# DC_Sensor_ESP8266_ADC_NC_10.net
KiCad netlist of a schematic drawn in EAGLE
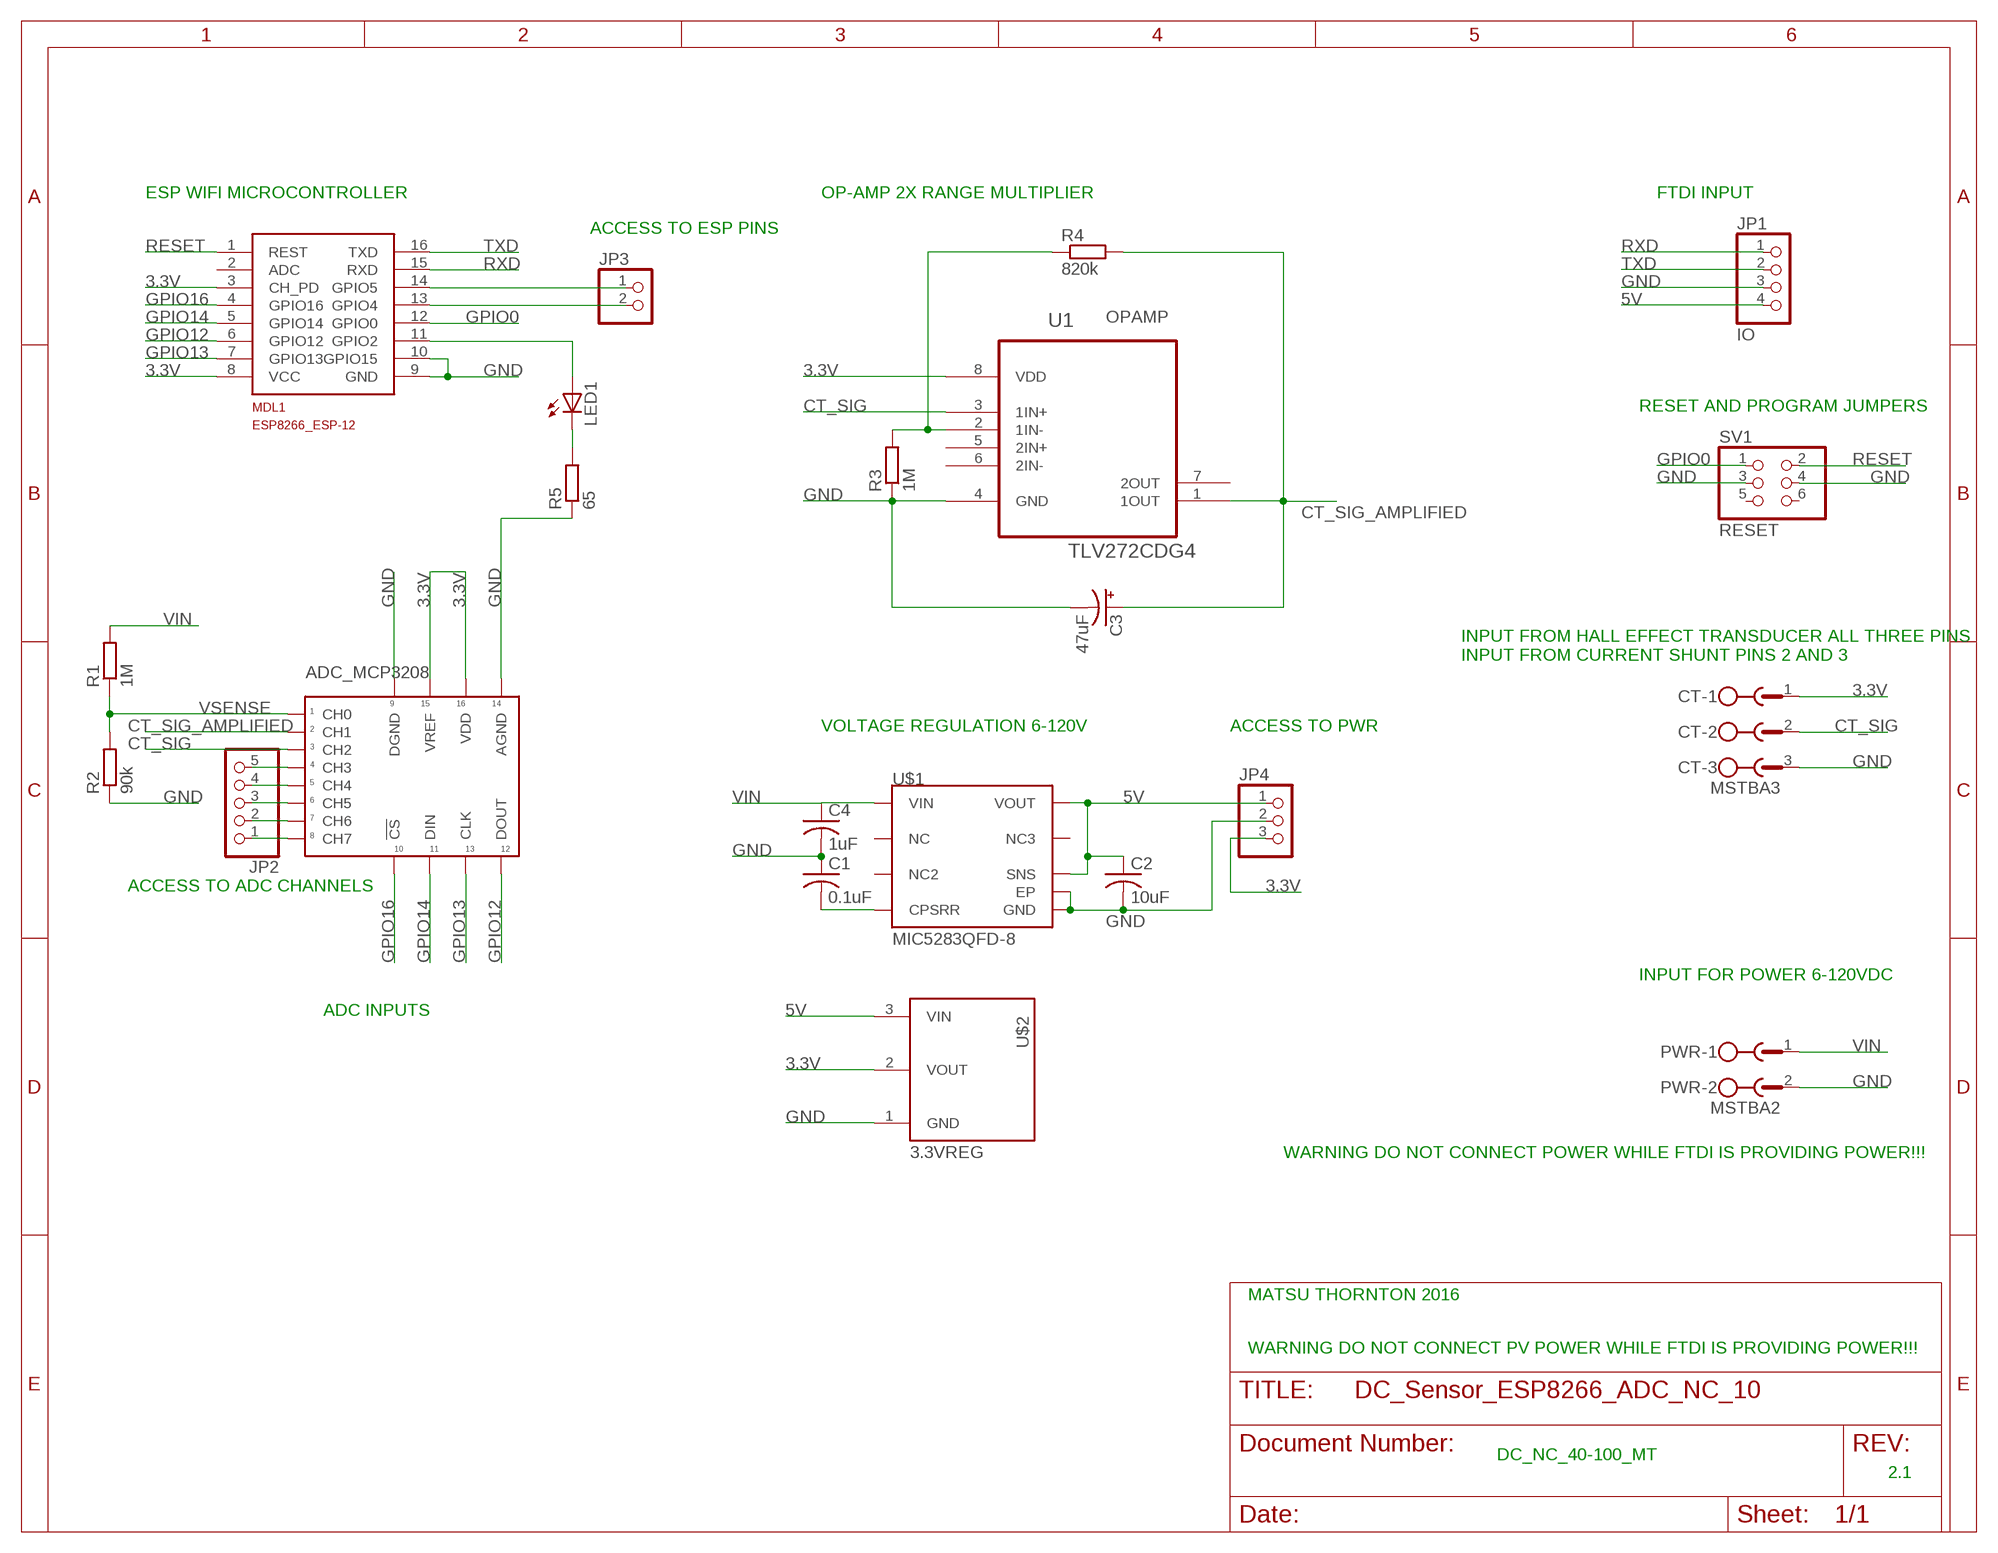
[diagram p0: schematic, sheet 1]

(export (version "E")
  (design (tool "Eeschema 10.0.6"))
  (components
    (comp (ref "ADC_MCP3208")
      (value "21298ESMD")
      (footprint "eagle-import:PDIP16")
      (libsource (lib "eagle-import") (part "21298ESMD"))
    )
    (comp (ref "C1")
      (value "0.1uF")
      (footprint "eagle-import:C0402")
      (libsource (lib "eagle-import") (part "C-USC0402"))
    )
    (comp (ref "C2")
      (value "10uF")
      (footprint "eagle-import:C0603K")
      (libsource (lib "eagle-import") (part "C-USC0603K"))
    )
    (comp (ref "C3")
      (value "47uF")
      (footprint "eagle-import:PANASONIC_C")
      (libsource (lib "eagle-import") (part "CPOL-USC"))
    )
    (comp (ref "C4")
      (value "1uF")
      (footprint "eagle-import:C2220K")
      (libsource (lib "eagle-import") (part "C-USC2220K"))
    )
    (comp (ref "CT")
      (value "MSTBA3")
      (footprint "eagle-import:MSTBA3")
      (fields (field (name "MF") "FARNELL") (field (name "MPN") "1757255"))
      (libsource (lib "eagle-import") (part "MSTBA3"))
    )
    (comp (ref "JP1")
      (value "IO")
      (footprint "eagle-import:1X04")
      (libsource (lib "eagle-import") (part "PINHD-1X4"))
    )
    (comp (ref "JP2")
      (value "PINHD-1X5")
      (footprint "eagle-import:1X05")
      (libsource (lib "eagle-import") (part "PINHD-1X5"))
    )
    (comp (ref "JP3")
      (value "PINHD-1X2")
      (footprint "eagle-import:1X02")
      (libsource (lib "eagle-import") (part "PINHD-1X2"))
    )
    (comp (ref "JP4")
      (value "PINHD-1X3")
      (footprint "eagle-import:1X03")
      (libsource (lib "eagle-import") (part "PINHD-1X3"))
    )
    (comp (ref "LED1")
      (value "LEDCHIP-LED0603")
      (footprint "eagle-import:CHIP-LED0603")
      (libsource (lib "eagle-import") (part "LEDCHIP-LED0603"))
    )
    (comp (ref "MDL1")
      (value "ESP8266-12GPIO04/05_CORRECTED")
      (footprint "eagle-import:ESP8266-ESP12")
      (libsource (lib "eagle-import") (part "ESP8266-12GPIO04/05_CORRECTED"))
    )
    (comp (ref "PWR")
      (value "MSTBA2")
      (footprint "eagle-import:MSTBA2")
      (fields (field (name "MF") "FARNELL") (field (name "MPN") "1757242"))
      (libsource (lib "eagle-import") (part "MSTBA2"))
    )
    (comp (ref "R1")
      (value "1M")
      (footprint "eagle-import:R0805")
      (libsource (lib "eagle-import") (part "R-EU_R0805"))
    )
    (comp (ref "R2")
      (value "90k")
      (footprint "eagle-import:R0805")
      (libsource (lib "eagle-import") (part "R-EU_R0805"))
    )
    (comp (ref "R3")
      (value "1M")
      (footprint "eagle-import:R0805")
      (libsource (lib "eagle-import") (part "R-EU_R0805"))
    )
    (comp (ref "R4")
      (value "820k")
      (footprint "eagle-import:R0805")
      (libsource (lib "eagle-import") (part "R-EU_R0805"))
    )
    (comp (ref "R5")
      (value "65")
      (footprint "eagle-import:R0805")
      (libsource (lib "eagle-import") (part "R-EU_R0805"))
    )
    (comp (ref "SV1")
      (value "RESET")
      (footprint "eagle-import:2X03")
      (libsource (lib "eagle-import") (part "PINHD-2X3"))
    )
    (comp (ref "U$1")
      (value "MIC5283QFD-8")
      (footprint "eagle-import:8-VDFN")
      (libsource (lib "eagle-import") (part "MIC5283QFD-8"))
    )
    (comp (ref "U$2")
      (value "3.3VREG")
      (footprint "eagle-import:3PVREG")
      (libsource (lib "eagle-import") (part "3.3VREG"))
    )
    (comp (ref "U1")
      (value "TLV272CDG4")
      (footprint "eagle-import:SOIC127P600X175-8N")
      (fields (field (name "TYPE") "OPAMP"))
      (libsource (lib "eagle-import") (part "TLV272CDG4"))
    )
  )
  (nets
    (net (code "1") (name "/3.3V") (class "Default")
      (node (ref "ADC_MCP3208") (pin "P$15") (pinfunction "VREF_P$15") (pintype "bidirectional"))
      (node (ref "ADC_MCP3208") (pin "P$16") (pinfunction "VDD_P$16") (pintype "bidirectional"))
      (node (ref "CT") (pin "1") (pinfunction "1_1") (pintype "passive"))
      (node (ref "JP4") (pin "3") (pinfunction "3_3") (pintype "passive"))
      (node (ref "MDL1") (pin "3") (pinfunction "CH_PD_3") (pintype "bidirectional"))
      (node (ref "MDL1") (pin "8") (pinfunction "VCC_8") (pintype "bidirectional"))
      (node (ref "U$2") (pin "2") (pinfunction "VOUT_2") (pintype "bidirectional"))
      (node (ref "U1") (pin "8") (pinfunction "VDD_8") (pintype "power_in"))
    )
    (net (code "2") (name "/5V") (class "Default")
      (node (ref "C2") (pin "1") (pinfunction "1_1") (pintype "passive"))
      (node (ref "JP1") (pin "4") (pinfunction "4_4") (pintype "passive"))
      (node (ref "JP4") (pin "1") (pinfunction "1_1") (pintype "passive"))
      (node (ref "U$1") (pin "P$6") (pinfunction "SNS_P$6") (pintype "input"))
      (node (ref "U$1") (pin "P$8") (pinfunction "VOUT_P$8") (pintype "output"))
      (node (ref "U$2") (pin "3") (pinfunction "VIN_3") (pintype "bidirectional"))
    )
    (net (code "3") (name "/CT_SIG") (class "Default")
      (node (ref "ADC_MCP3208") (pin "P$3") (pinfunction "CH2_P$3") (pintype "bidirectional"))
      (node (ref "CT") (pin "2") (pinfunction "1_2") (pintype "passive"))
      (node (ref "U1") (pin "3") (pinfunction "1IN+_3") (pintype "input"))
    )
    (net (code "4") (name "/CT_SIG_AMPLIFIED") (class "Default")
      (node (ref "ADC_MCP3208") (pin "P$2") (pinfunction "CH1_P$2") (pintype "bidirectional"))
      (node (ref "C3") (pin "+") (pinfunction "+_+") (pintype "passive"))
      (node (ref "R4") (pin "2") (pinfunction "2_2") (pintype "passive"))
      (node (ref "U1") (pin "1") (pinfunction "1OUT_1") (pintype "output"))
    )
    (net (code "5") (name "/GND") (class "Default")
      (node (ref "ADC_MCP3208") (pin "P$14") (pinfunction "AGND_P$14") (pintype "bidirectional"))
      (node (ref "ADC_MCP3208") (pin "P$9") (pinfunction "DGND_P$9") (pintype "bidirectional"))
      (node (ref "C1") (pin "1") (pinfunction "1_1") (pintype "passive"))
      (node (ref "C2") (pin "2") (pinfunction "2_2") (pintype "passive"))
      (node (ref "C3") (pin "-") (pinfunction "-_-") (pintype "passive"))
      (node (ref "C4") (pin "2") (pinfunction "2_2") (pintype "passive"))
      (node (ref "CT") (pin "3") (pinfunction "1_3") (pintype "passive"))
      (node (ref "JP1") (pin "3") (pinfunction "3_3") (pintype "passive"))
      (node (ref "JP4") (pin "2") (pinfunction "2_2") (pintype "passive"))
      (node (ref "MDL1") (pin "10") (pinfunction "GPIO15_10") (pintype "bidirectional"))
      (node (ref "MDL1") (pin "9") (pinfunction "GND_9") (pintype "bidirectional"))
      (node (ref "PWR") (pin "2") (pinfunction "1_2") (pintype "passive"))
      (node (ref "R2") (pin "1") (pinfunction "1_1") (pintype "passive"))
      (node (ref "R3") (pin "1") (pinfunction "1_1") (pintype "passive"))
      (node (ref "R5") (pin "1") (pinfunction "1_1") (pintype "passive"))
      (node (ref "SV1") (pin "3") (pinfunction "3_3") (pintype "passive"))
      (node (ref "SV1") (pin "4") (pinfunction "4_4") (pintype "passive"))
      (node (ref "U$1") (pin "EXP") (pinfunction "EP_EXP") (pintype "bidirectional"))
      (node (ref "U$1") (pin "P$5") (pinfunction "GND_P$5") (pintype "power_in"))
      (node (ref "U$2") (pin "1") (pinfunction "GND_1") (pintype "bidirectional"))
      (node (ref "U1") (pin "4") (pinfunction "GND_4") (pintype "passive"))
    )
    (net (code "6") (name "/GPIO0") (class "Default")
      (node (ref "MDL1") (pin "12") (pinfunction "GPIO0_12") (pintype "bidirectional"))
      (node (ref "SV1") (pin "1") (pinfunction "1_1") (pintype "passive"))
    )
    (net (code "7") (name "/GPIO12") (class "Default")
      (node (ref "ADC_MCP3208") (pin "P$12") (pinfunction "DOUT_P$12") (pintype "bidirectional"))
      (node (ref "MDL1") (pin "6") (pinfunction "GPIO12_6") (pintype "bidirectional"))
    )
    (net (code "8") (name "/GPIO13") (class "Default")
      (node (ref "ADC_MCP3208") (pin "P$13") (pinfunction "CLK_P$13") (pintype "bidirectional"))
      (node (ref "MDL1") (pin "7") (pinfunction "GPIO13_7") (pintype "bidirectional"))
    )
    (net (code "9") (name "/GPIO14") (class "Default")
      (node (ref "ADC_MCP3208") (pin "P$11") (pinfunction "DIN_P$11") (pintype "bidirectional"))
      (node (ref "MDL1") (pin "5") (pinfunction "GPIO14_5") (pintype "bidirectional"))
    )
    (net (code "10") (name "/GPIO16") (class "Default")
      (node (ref "ADC_MCP3208") (pin "P$10") (pinfunction "~{CS}_P$10") (pintype "bidirectional"))
      (node (ref "MDL1") (pin "4") (pinfunction "GPIO16_4") (pintype "bidirectional"))
    )
    (net (code "11") (name "/RESET") (class "Default")
      (node (ref "MDL1") (pin "1") (pinfunction "REST_1") (pintype "bidirectional"))
      (node (ref "SV1") (pin "2") (pinfunction "2_2") (pintype "passive"))
    )
    (net (code "12") (name "/RXD") (class "Default")
      (node (ref "JP1") (pin "1") (pinfunction "1_1") (pintype "passive"))
      (node (ref "MDL1") (pin "15") (pinfunction "RXD_15") (pintype "bidirectional"))
    )
    (net (code "13") (name "/TXD") (class "Default")
      (node (ref "JP1") (pin "2") (pinfunction "2_2") (pintype "passive"))
      (node (ref "MDL1") (pin "16") (pinfunction "TXD_16") (pintype "bidirectional"))
    )
    (net (code "14") (name "/VIN") (class "Default")
      (node (ref "C4") (pin "1") (pinfunction "1_1") (pintype "passive"))
      (node (ref "PWR") (pin "1") (pinfunction "1_1") (pintype "passive"))
      (node (ref "R1") (pin "2") (pinfunction "2_2") (pintype "passive"))
      (node (ref "U$1") (pin "P$1") (pinfunction "VIN_P$1") (pintype "input"))
    )
    (net (code "15") (name "/VSENSE") (class "Default")
      (node (ref "ADC_MCP3208") (pin "P$1") (pinfunction "CH0_P$1") (pintype "bidirectional"))
      (node (ref "R1") (pin "1") (pinfunction "1_1") (pintype "passive"))
      (node (ref "R2") (pin "2") (pinfunction "2_2") (pintype "passive"))
    )
    (net (code "16") (name "Net-(ADC_MCP3208-CH3)") (class "Default")
      (node (ref "ADC_MCP3208") (pin "P$4") (pinfunction "CH3_P$4") (pintype "bidirectional"))
      (node (ref "JP2") (pin "5") (pinfunction "5_5") (pintype "passive"))
    )
    (net (code "17") (name "Net-(ADC_MCP3208-CH4)") (class "Default")
      (node (ref "ADC_MCP3208") (pin "P$5") (pinfunction "CH4_P$5") (pintype "bidirectional"))
      (node (ref "JP2") (pin "4") (pinfunction "4_4") (pintype "passive"))
    )
    (net (code "18") (name "Net-(ADC_MCP3208-CH5)") (class "Default")
      (node (ref "ADC_MCP3208") (pin "P$6") (pinfunction "CH5_P$6") (pintype "bidirectional"))
      (node (ref "JP2") (pin "3") (pinfunction "3_3") (pintype "passive"))
    )
    (net (code "19") (name "Net-(ADC_MCP3208-CH6)") (class "Default")
      (node (ref "ADC_MCP3208") (pin "P$7") (pinfunction "CH6_P$7") (pintype "bidirectional"))
      (node (ref "JP2") (pin "2") (pinfunction "2_2") (pintype "passive"))
    )
    (net (code "20") (name "Net-(ADC_MCP3208-CH7)") (class "Default")
      (node (ref "ADC_MCP3208") (pin "P$8") (pinfunction "CH7_P$8") (pintype "bidirectional"))
      (node (ref "JP2") (pin "1") (pinfunction "1_1") (pintype "passive"))
    )
    (net (code "21") (name "Net-(LED1-PadC)") (class "Default")
      (node (ref "LED1") (pin "C") (pinfunction "C_C") (pintype "passive"))
      (node (ref "R5") (pin "2") (pinfunction "2_2") (pintype "passive"))
    )
    (net (code "22") (name "Net-(MDL1-GPIO2)") (class "Default")
      (node (ref "LED1") (pin "A") (pinfunction "A_A") (pintype "passive"))
      (node (ref "MDL1") (pin "11") (pinfunction "GPIO2_11") (pintype "bidirectional"))
    )
    (net (code "23") (name "Net-(MDL1-GPIO4)") (class "Default")
      (node (ref "JP3") (pin "2") (pinfunction "2_2") (pintype "passive"))
      (node (ref "MDL1") (pin "13") (pinfunction "GPIO4_13") (pintype "bidirectional"))
    )
    (net (code "24") (name "Net-(MDL1-GPIO5)") (class "Default")
      (node (ref "JP3") (pin "1") (pinfunction "1_1") (pintype "passive"))
      (node (ref "MDL1") (pin "14") (pinfunction "GPIO5_14") (pintype "bidirectional"))
    )
    (net (code "25") (name "Net-(U$1-CPSRR)") (class "Default")
      (node (ref "C1") (pin "2") (pinfunction "2_2") (pintype "passive"))
      (node (ref "U$1") (pin "P$4") (pinfunction "CPSRR_P$4") (pintype "input"))
    )
    (net (code "26") (name "Net-(U1-1IN-)") (class "Default")
      (node (ref "R3") (pin "2") (pinfunction "2_2") (pintype "passive"))
      (node (ref "R4") (pin "1") (pinfunction "1_1") (pintype "passive"))
      (node (ref "U1") (pin "2") (pinfunction "1IN-_2") (pintype "input"))
    )
    (net (code "27") (name "unconnected-(MDL1-ADC-Pad2)") (class "Default")
      (node (ref "MDL1") (pin "2") (pinfunction "ADC_2") (pintype "bidirectional"))
    )
    (net (code "28") (name "unconnected-(SV1-Pad5)") (class "Default")
      (node (ref "SV1") (pin "5") (pinfunction "5_5") (pintype "passive"))
    )
    (net (code "29") (name "unconnected-(SV1-Pad6)") (class "Default")
      (node (ref "SV1") (pin "6") (pinfunction "6_6") (pintype "passive"))
    )
    (net (code "30") (name "unconnected-(U$1-NC-PadP$2)") (class "Default")
      (node (ref "U$1") (pin "P$2") (pinfunction "NC_P$2") (pintype "input"))
    )
    (net (code "31") (name "unconnected-(U$1-NC2-PadP$3)") (class "Default")
      (node (ref "U$1") (pin "P$3") (pinfunction "NC2_P$3") (pintype "input"))
    )
    (net (code "32") (name "unconnected-(U$1-NC3-PadP$7)") (class "Default")
      (node (ref "U$1") (pin "P$7") (pinfunction "NC3_P$7") (pintype "output"))
    )
    (net (code "33") (name "unconnected-(U1-2IN+-Pad5)") (class "Default")
      (node (ref "U1") (pin "5") (pinfunction "2IN+_5") (pintype "input"))
    )
    (net (code "34") (name "unconnected-(U1-2IN--Pad6)") (class "Default")
      (node (ref "U1") (pin "6") (pinfunction "2IN-_6") (pintype "input"))
    )
    (net (code "35") (name "unconnected-(U1-2OUT-Pad7)") (class "Default")
      (node (ref "U1") (pin "7") (pinfunction "2OUT_7") (pintype "output"))
    )
  )
)
